# murri.net
KiCad netlist of a schematic drawn in Altium Designer
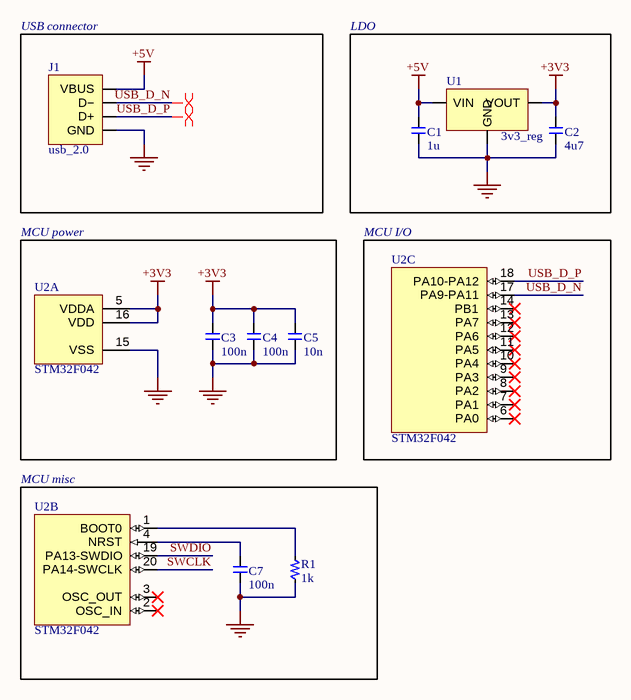
[diagram p0: murri.SchDoc]

(export (version "E")
  (design (tool "Eeschema 10.0.6"))
  (components
    (comp (ref "C1")
      (value "1u")
      (footprint "C0402")
      (description "0402 cap")
      (libsource (lib "murri") (part "C_0402"))
    )
    (comp (ref "C2")
      (value "4u7")
      (footprint "C0402")
      (description "0402 cap")
      (libsource (lib "murri") (part "C_0402"))
    )
    (comp (ref "C3")
      (value "100n")
      (footprint "C0402")
      (description "0402 cap")
      (libsource (lib "murri") (part "C_0402"))
    )
    (comp (ref "C4")
      (value "100n")
      (footprint "C0402")
      (description "0402 cap")
      (libsource (lib "murri") (part "C_0402"))
    )
    (comp (ref "C5")
      (value "10n")
      (footprint "C0402")
      (description "0402 cap")
      (libsource (lib "murri") (part "C_0402"))
    )
    (comp (ref "C7")
      (value "100n")
      (footprint "C0402")
      (description "0402 cap")
      (libsource (lib "murri") (part "C_0402"))
    )
    (comp (ref "J1")
      (value "usb_2.0")
      (footprint "USB_20")
      (description "USB 2.0 PCB")
      (libsource (lib "murri") (part "USB_20"))
    )
    (comp (ref "R1")
      (value "1k")
      (footprint "R0402")
      (description "0402 62.5mW")
      (libsource (lib "murri") (part "R_0402"))
    )
    (comp (ref "U1")
      (value "3v3_reg")
      (footprint "SOT23_torex")
      (libsource (lib "murri") (part "XC6206P332MR-G"))
    )
    (comp (ref "U2")
      (value "STM32F042")
      (footprint "TSSOP20_ST")
      (description "32KB 1.65V~3.6V ARM-M0 48MHz 16 TSSOP-20(4.4x6.5) Microcontrollers (MCU/MPU/SOC) ROHS")
      (libsource (lib "murri") (part "STM32F042F6P6TR"))
    )
  )
  (nets
    (net (code "1") (name "+3V3") (class "Default")
      (node (ref "C2") (pin "2") (pinfunction "2_2") (pintype "passive"))
      (node (ref "C3") (pin "2") (pinfunction "2_2") (pintype "passive"))
      (node (ref "C4") (pin "2") (pinfunction "2_2") (pintype "passive"))
      (node (ref "C5") (pin "2") (pinfunction "2_2") (pintype "passive"))
      (node (ref "U1") (pin "2") (pinfunction "VOUT_2") (pintype "passive"))
      (node (ref "U2") (pin "16") (pinfunction "VDD_16") (pintype "power_in"))
      (node (ref "U2") (pin "5") (pinfunction "VDDA_5") (pintype "power_in"))
    )
    (net (code "2") (name "+5V") (class "Default")
      (node (ref "C1") (pin "2") (pinfunction "2_2") (pintype "passive"))
      (node (ref "J1") (pin "1") (pinfunction "VBUS_1") (pintype "passive"))
      (node (ref "U1") (pin "3") (pinfunction "VIN_3") (pintype "passive"))
    )
    (net (code "3") (name "/SWCLK") (class "Default")
      (node (ref "U2") (pin "20") (pinfunction "PA14-SWCLK_20") (pintype "bidirectional"))
    )
    (net (code "4") (name "/SWDIO") (class "Default")
      (node (ref "U2") (pin "19") (pinfunction "PA13-SWDIO_19") (pintype "bidirectional"))
    )
    (net (code "5") (name "/USB_D_N") (class "Default")
      (node (ref "J1") (pin "2") (pinfunction "D−_2") (pintype "passive"))
      (node (ref "U2") (pin "17") (pinfunction "PA9-PA11_17") (pintype "bidirectional"))
    )
    (net (code "6") (name "/USB_D_P") (class "Default")
      (node (ref "J1") (pin "3") (pinfunction "D+_3") (pintype "passive"))
      (node (ref "U2") (pin "18") (pinfunction "PA10-PA12_18") (pintype "bidirectional"))
    )
    (net (code "7") (name "GND") (class "Default")
      (node (ref "C1") (pin "1") (pinfunction "1_1") (pintype "passive"))
      (node (ref "C2") (pin "1") (pinfunction "1_1") (pintype "passive"))
      (node (ref "C3") (pin "1") (pinfunction "1_1") (pintype "passive"))
      (node (ref "C4") (pin "1") (pinfunction "1_1") (pintype "passive"))
      (node (ref "C5") (pin "1") (pinfunction "1_1") (pintype "passive"))
      (node (ref "C7") (pin "1") (pinfunction "1_1") (pintype "passive"))
      (node (ref "J1") (pin "4") (pinfunction "GND_4") (pintype "passive"))
      (node (ref "R1") (pin "1") (pinfunction "1_1") (pintype "passive"))
      (node (ref "U1") (pin "1") (pinfunction "GND_1") (pintype "passive"))
      (node (ref "U2") (pin "15") (pinfunction "VSS_15") (pintype "power_in"))
    )
    (net (code "8") (name "Net-(U2B-BOOT0)") (class "Default")
      (node (ref "R1") (pin "2") (pinfunction "2_2") (pintype "passive"))
      (node (ref "U2") (pin "1") (pinfunction "BOOT0_1") (pintype "bidirectional"))
    )
    (net (code "9") (name "Net-(U2B-NRST)") (class "Default")
      (node (ref "C7") (pin "2") (pinfunction "2_2") (pintype "passive"))
      (node (ref "U2") (pin "4") (pinfunction "NRST_4") (pintype "input"))
    )
    (net (code "10") (name "unconnected-(U2B-OSC_IN-Pad2)") (class "Default")
      (node (ref "U2") (pin "2") (pinfunction "OSC_IN_2") (pintype "bidirectional+no_connect"))
    )
    (net (code "11") (name "unconnected-(U2B-OSC_OUT-Pad3)") (class "Default")
      (node (ref "U2") (pin "3") (pinfunction "OSC_OUT_3") (pintype "bidirectional+no_connect"))
    )
    (net (code "12") (name "unconnected-(U2C-PA0-Pad6)") (class "Default")
      (node (ref "U2") (pin "6") (pinfunction "PA0_6") (pintype "bidirectional+no_connect"))
    )
    (net (code "13") (name "unconnected-(U2C-PA1-Pad7)") (class "Default")
      (node (ref "U2") (pin "7") (pinfunction "PA1_7") (pintype "bidirectional+no_connect"))
    )
    (net (code "14") (name "unconnected-(U2C-PA2-Pad8)") (class "Default")
      (node (ref "U2") (pin "8") (pinfunction "PA2_8") (pintype "bidirectional+no_connect"))
    )
    (net (code "15") (name "unconnected-(U2C-PA3-Pad9)") (class "Default")
      (node (ref "U2") (pin "9") (pinfunction "PA3_9") (pintype "bidirectional+no_connect"))
    )
    (net (code "16") (name "unconnected-(U2C-PA4-Pad10)") (class "Default")
      (node (ref "U2") (pin "10") (pinfunction "PA4_10") (pintype "bidirectional+no_connect"))
    )
    (net (code "17") (name "unconnected-(U2C-PA5-Pad11)") (class "Default")
      (node (ref "U2") (pin "11") (pinfunction "PA5_11") (pintype "bidirectional+no_connect"))
    )
    (net (code "18") (name "unconnected-(U2C-PA6-Pad12)") (class "Default")
      (node (ref "U2") (pin "12") (pinfunction "PA6_12") (pintype "bidirectional+no_connect"))
    )
    (net (code "19") (name "unconnected-(U2C-PA7-Pad13)") (class "Default")
      (node (ref "U2") (pin "13") (pinfunction "PA7_13") (pintype "bidirectional+no_connect"))
    )
    (net (code "20") (name "unconnected-(U2C-PB1-Pad14)") (class "Default")
      (node (ref "U2") (pin "14") (pinfunction "PB1_14") (pintype "bidirectional+no_connect"))
    )
  )
)
